# placa_esp_30_pins_V1.net
KiCad netlist of a schematic drawn in EAGLE
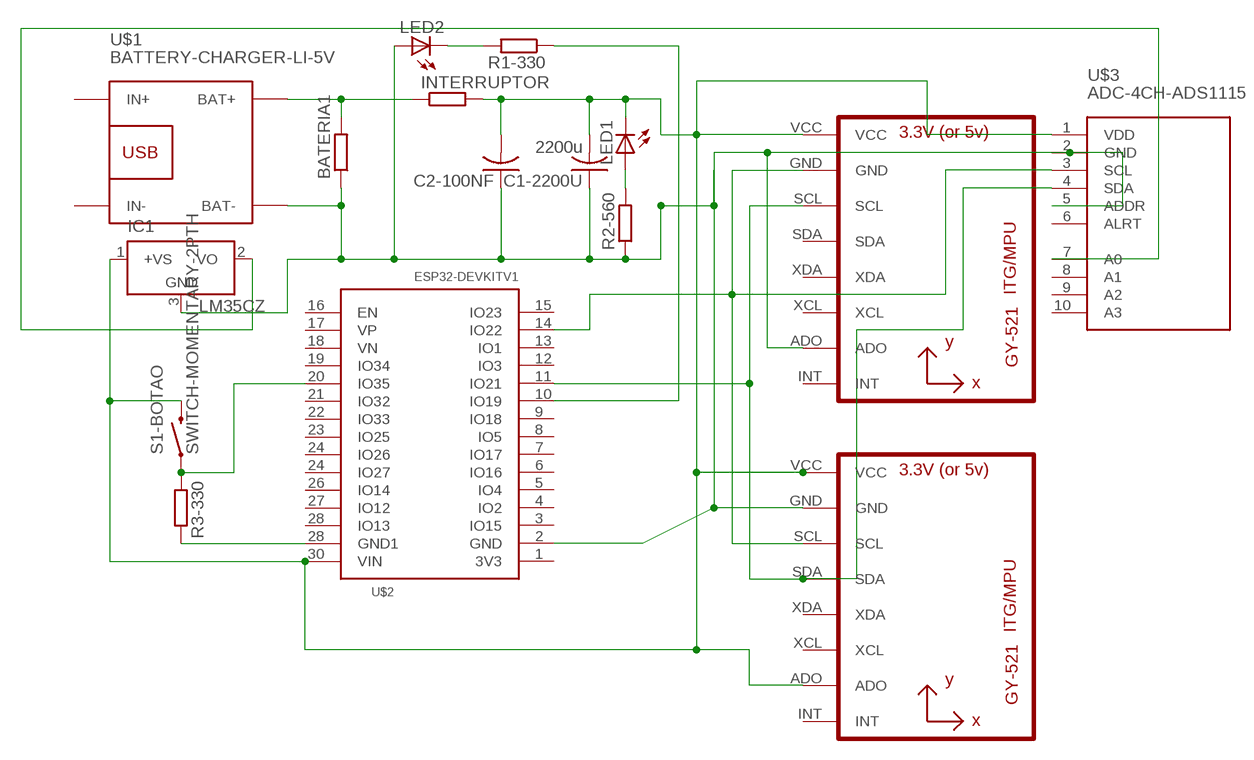
[diagram p0: schematic, sheet 1]

(export (version "E")
  (design (tool "Eeschema 10.0.6"))
  (components
    (comp (ref "BATERIA1")
      (value "R-EU_0207/10")
      (footprint "eagle-import:0207_10")
      (libsource (lib "eagle-import") (part "R-EU_0207/10"))
    )
    (comp (ref "C1-2200U")
      (value "2200u")
      (footprint "eagle-import:C025-060X050")
      (libsource (lib "eagle-import") (part "C-US025-060X050"))
    )
    (comp (ref "C2-100NF")
      (value "C-US025-060X050")
      (footprint "eagle-import:C025-060X050")
      (libsource (lib "eagle-import") (part "C-US025-060X050"))
    )
    (comp (ref "IC1")
      (value "LM35CZ")
      (footprint "eagle-import:TO92")
      (libsource (lib "eagle-import") (part "LM35CZ"))
    )
    (comp (ref "INTERRUPTOR")
      (value "R-EU_0207/7")
      (footprint "eagle-import:0207_7")
      (libsource (lib "eagle-import") (part "R-EU_0207/7"))
    )
    (comp (ref "LED1")
      (value "LEDLD260")
      (footprint "eagle-import:LD260")
      (libsource (lib "eagle-import") (part "LEDLD260"))
    )
    (comp (ref "LED2")
      (value "LEDLD260")
      (footprint "eagle-import:LD260")
      (libsource (lib "eagle-import") (part "LEDLD260"))
    )
    (comp (ref "OXIMETRO")
      (value "GY-521MPU6050")
      (footprint "eagle-import:GY-521")
      (libsource (lib "eagle-import") (part "GY-521MPU6050"))
    )
    (comp (ref "R1-330")
      (value "R-EU_0207/10")
      (footprint "eagle-import:0207_10")
      (libsource (lib "eagle-import") (part "R-EU_0207/10"))
    )
    (comp (ref "R2-560")
      (value "R-EU_0207/10")
      (footprint "eagle-import:0207_10")
      (libsource (lib "eagle-import") (part "R-EU_0207/10"))
    )
    (comp (ref "R3-330")
      (value "R-EU_0207/10")
      (footprint "eagle-import:0207_10")
      (libsource (lib "eagle-import") (part "R-EU_0207/10"))
    )
    (comp (ref "S1-BOTAO")
      (value "SWITCH-MOMENTARY-2PTH")
      (footprint "eagle-import:TACTILE-PTH")
      (libsource (lib "eagle-import") (part "SWITCH-MOMENTARY-2PTH"))
    )
    (comp (ref "U$1")
      (value "BATTERY-CHARGER-LI-5V")
      (footprint "eagle-import:BATTERY-CHARGER-LI-5V")
      (libsource (lib "eagle-import") (part "BATTERY-CHARGER-LI-5V"))
    )
    (comp (ref "U$2")
      (value "ESP32DEVKITV1")
      (footprint "eagle-import:ESP32-DEVKITV1")
      (libsource (lib "eagle-import") (part "ESP32DEVKITV1"))
    )
    (comp (ref "U$3")
      (value "ADC-4CH-ADS1115")
      (footprint "eagle-import:ADC-4CH-ADS1115")
      (libsource (lib "eagle-import") (part "ADC-4CH-ADS1115"))
    )
    (comp (ref "U2")
      (value "GY-521MPU6050")
      (footprint "eagle-import:GY-521")
      (libsource (lib "eagle-import") (part "GY-521MPU6050"))
    )
  )
  (nets
    (net (code "1") (name "Net-(BATERIA1-Pad2)") (class "Default")
      (node (ref "BATERIA1") (pin "2") (pinfunction "2_2") (pintype "passive"))
      (node (ref "INTERRUPTOR") (pin "1") (pinfunction "1_1") (pintype "passive"))
      (node (ref "U$1") (pin "BAT+") (pinfunction "BAT+_BAT+") (pintype "bidirectional"))
    )
    (net (code "2") (name "Net-(IC1-+VS)") (class "Default")
      (node (ref "C1-2200U") (pin "2") (pinfunction "2_2") (pintype "passive"))
      (node (ref "C2-100NF") (pin "2") (pinfunction "2_2") (pintype "passive"))
      (node (ref "IC1") (pin "1") (pinfunction "+VS_1") (pintype "input"))
      (node (ref "INTERRUPTOR") (pin "2") (pinfunction "2_2") (pintype "passive"))
      (node (ref "LED1") (pin "K") (pinfunction "C_K") (pintype "passive"))
      (node (ref "OXIMETRO") (pin "VCC") (pinfunction "VCC_VCC") (pintype "bidirectional"))
      (node (ref "S1-BOTAO") (pin "3") (pinfunction "2_3") (pintype "passive"))
      (node (ref "U$2") (pin "30") (pinfunction "VIN_30") (pintype "bidirectional"))
      (node (ref "U$3") (pin "1") (pinfunction "VDD_1") (pintype "power_in"))
      (node (ref "U2") (pin "ADO") (pinfunction "ADO_ADO") (pintype "bidirectional"))
      (node (ref "U2") (pin "VCC") (pinfunction "VCC_VCC") (pintype "bidirectional"))
    )
    (net (code "3") (name "Net-(IC1-GND)") (class "Default")
      (node (ref "BATERIA1") (pin "1") (pinfunction "1_1") (pintype "passive"))
      (node (ref "C1-2200U") (pin "1") (pinfunction "1_1") (pintype "passive"))
      (node (ref "C2-100NF") (pin "1") (pinfunction "1_1") (pintype "passive"))
      (node (ref "IC1") (pin "3") (pinfunction "GND_3") (pintype "power_in"))
      (node (ref "LED2") (pin "A") (pinfunction "A_A") (pintype "passive"))
      (node (ref "OXIMETRO") (pin "ADO") (pinfunction "ADO_ADO") (pintype "bidirectional"))
      (node (ref "R2-560") (pin "1") (pinfunction "1_1") (pintype "passive"))
      (node (ref "U$1") (pin "BAT-") (pinfunction "BAT-_BAT-") (pintype "bidirectional"))
      (node (ref "U$2") (pin "2") (pinfunction "GND_2") (pintype "bidirectional"))
      (node (ref "U$3") (pin "2") (pinfunction "GND_2") (pintype "power_in"))
      (node (ref "U$3") (pin "5") (pinfunction "ADDR_5") (pintype "bidirectional"))
      (node (ref "U2") (pin "GND") (pinfunction "GND_GND") (pintype "bidirectional"))
    )
    (net (code "4") (name "Net-(IC1-VO)") (class "Default")
      (node (ref "IC1") (pin "2") (pinfunction "VO_2") (pintype "input"))
      (node (ref "U$3") (pin "7") (pinfunction "A0_7") (pintype "input"))
    )
    (net (code "5") (name "Net-(LED1-PadA)") (class "Default")
      (node (ref "LED1") (pin "A") (pinfunction "A_A") (pintype "passive"))
      (node (ref "R2-560") (pin "2") (pinfunction "2_2") (pintype "passive"))
    )
    (net (code "6") (name "Net-(LED2-C)") (class "Default")
      (node (ref "LED2") (pin "K") (pinfunction "C_K") (pintype "passive"))
      (node (ref "R1-330") (pin "2") (pinfunction "2_2") (pintype "passive"))
    )
    (net (code "7") (name "Net-(U$2-GND1)") (class "Default")
      (node (ref "R3-330") (pin "2") (pinfunction "2_2") (pintype "passive"))
      (node (ref "U$2") (pin "28") (pinfunction "GND1_28") (pintype "bidirectional"))
    )
    (net (code "8") (name "Net-(U$2-IO19)") (class "Default")
      (node (ref "R1-330") (pin "1") (pinfunction "1_1") (pintype "passive"))
      (node (ref "U$2") (pin "10") (pinfunction "IO19_10") (pintype "bidirectional"))
    )
    (net (code "9") (name "Net-(U$2-IO21)") (class "Default")
      (node (ref "OXIMETRO") (pin "SCL") (pinfunction "SCL_SCL") (pintype "bidirectional"))
      (node (ref "U$2") (pin "11") (pinfunction "IO21_11") (pintype "bidirectional"))
      (node (ref "U$3") (pin "4") (pinfunction "SDA_4") (pintype "bidirectional"))
      (node (ref "U2") (pin "SDA") (pinfunction "SDA_SDA") (pintype "bidirectional"))
    )
    (net (code "10") (name "Net-(U$2-IO22)") (class "Default")
      (node (ref "OXIMETRO") (pin "GND") (pinfunction "GND_GND") (pintype "bidirectional"))
      (node (ref "U$2") (pin "14") (pinfunction "IO22_14") (pintype "bidirectional"))
      (node (ref "U$3") (pin "3") (pinfunction "SCL_3") (pintype "bidirectional"))
      (node (ref "U2") (pin "SCL") (pinfunction "SCL_SCL") (pintype "bidirectional"))
    )
    (net (code "11") (name "Net-(U$2-IO35)") (class "Default")
      (node (ref "R3-330") (pin "1") (pinfunction "1_1") (pintype "passive"))
      (node (ref "S1-BOTAO") (pin "1") (pinfunction "1_1") (pintype "passive"))
      (node (ref "U$2") (pin "20") (pinfunction "IO35_20") (pintype "bidirectional"))
    )
    (net (code "12") (name "unconnected-(OXIMETRO-PadINT)") (class "Default")
      (node (ref "OXIMETRO") (pin "INT") (pinfunction "INT_INT") (pintype "bidirectional"))
    )
    (net (code "13") (name "unconnected-(OXIMETRO-PadSDA)") (class "Default")
      (node (ref "OXIMETRO") (pin "SDA") (pinfunction "SDA_SDA") (pintype "bidirectional"))
    )
    (net (code "14") (name "unconnected-(OXIMETRO-PadXCL)") (class "Default")
      (node (ref "OXIMETRO") (pin "XCL") (pinfunction "XCL_XCL") (pintype "bidirectional"))
    )
    (net (code "15") (name "unconnected-(OXIMETRO-PadXDA)") (class "Default")
      (node (ref "OXIMETRO") (pin "XDA") (pinfunction "XDA_XDA") (pintype "bidirectional"))
    )
    (net (code "16") (name "unconnected-(U$1-PadIN+)") (class "Default")
      (node (ref "U$1") (pin "IN+") (pinfunction "IN+_IN+") (pintype "bidirectional"))
    )
    (net (code "17") (name "unconnected-(U$1-PadIN-)") (class "Default")
      (node (ref "U$1") (pin "IN-") (pinfunction "IN-_IN-") (pintype "bidirectional"))
    )
    (net (code "18") (name "unconnected-(U$2-3V3-Pad1)") (class "Default")
      (node (ref "U$2") (pin "1") (pinfunction "3V3_1") (pintype "bidirectional"))
    )
    (net (code "19") (name "unconnected-(U$2-EN-Pad16)") (class "Default")
      (node (ref "U$2") (pin "16") (pinfunction "EN_16") (pintype "bidirectional"))
    )
    (net (code "20") (name "unconnected-(U$2-IO1-Pad13)") (class "Default")
      (node (ref "U$2") (pin "13") (pinfunction "IO1_13") (pintype "bidirectional"))
    )
    (net (code "21") (name "unconnected-(U$2-IO2-Pad4)") (class "Default")
      (node (ref "U$2") (pin "4") (pinfunction "IO2_4") (pintype "bidirectional"))
    )
    (net (code "22") (name "unconnected-(U$2-IO3-Pad12)") (class "Default")
      (node (ref "U$2") (pin "12") (pinfunction "IO3_12") (pintype "bidirectional"))
    )
    (net (code "23") (name "unconnected-(U$2-IO4-Pad5)") (class "Default")
      (node (ref "U$2") (pin "5") (pinfunction "IO4_5") (pintype "bidirectional"))
    )
    (net (code "24") (name "unconnected-(U$2-IO5-Pad8)") (class "Default")
      (node (ref "U$2") (pin "8") (pinfunction "IO5_8") (pintype "bidirectional"))
    )
    (net (code "25") (name "unconnected-(U$2-IO12-Pad27)") (class "Default")
      (node (ref "U$2") (pin "27") (pinfunction "IO12_27") (pintype "bidirectional"))
    )
    (net (code "26") (name "unconnected-(U$2-IO13-Pad28)") (class "Default")
      (node (ref "U$2") (pin "28") (pinfunction "IO13_28") (pintype "bidirectional"))
    )
    (net (code "27") (name "unconnected-(U$2-IO14-Pad26)") (class "Default")
      (node (ref "U$2") (pin "26") (pinfunction "IO14_26") (pintype "bidirectional"))
    )
    (net (code "28") (name "unconnected-(U$2-IO15-Pad3)") (class "Default")
      (node (ref "U$2") (pin "3") (pinfunction "IO15_3") (pintype "bidirectional"))
    )
    (net (code "29") (name "unconnected-(U$2-IO16-Pad6)") (class "Default")
      (node (ref "U$2") (pin "6") (pinfunction "IO16_6") (pintype "bidirectional"))
    )
    (net (code "30") (name "unconnected-(U$2-IO17-Pad7)") (class "Default")
      (node (ref "U$2") (pin "7") (pinfunction "IO17_7") (pintype "bidirectional"))
    )
    (net (code "31") (name "unconnected-(U$2-IO18-Pad9)") (class "Default")
      (node (ref "U$2") (pin "9") (pinfunction "IO18_9") (pintype "bidirectional"))
    )
    (net (code "32") (name "unconnected-(U$2-IO23-Pad15)") (class "Default")
      (node (ref "U$2") (pin "15") (pinfunction "IO23_15") (pintype "bidirectional"))
    )
    (net (code "33") (name "unconnected-(U$2-IO25-Pad23)") (class "Default")
      (node (ref "U$2") (pin "23") (pinfunction "IO25_23") (pintype "bidirectional"))
    )
    (net (code "34") (name "unconnected-(U$2-IO26-Pad24)") (class "Default")
      (node (ref "U$2") (pin "24") (pinfunction "IO26_24") (pintype "bidirectional"))
    )
    (net (code "35") (name "unconnected-(U$2-IO27-Pad24)") (class "Default")
      (node (ref "U$2") (pin "24") (pinfunction "IO27_24") (pintype "bidirectional"))
    )
    (net (code "36") (name "unconnected-(U$2-IO32-Pad21)") (class "Default")
      (node (ref "U$2") (pin "21") (pinfunction "IO32_21") (pintype "bidirectional"))
    )
    (net (code "37") (name "unconnected-(U$2-IO33-Pad22)") (class "Default")
      (node (ref "U$2") (pin "22") (pinfunction "IO33_22") (pintype "bidirectional"))
    )
    (net (code "38") (name "unconnected-(U$2-IO34-Pad19)") (class "Default")
      (node (ref "U$2") (pin "19") (pinfunction "IO34_19") (pintype "bidirectional"))
    )
    (net (code "39") (name "unconnected-(U$2-VN-Pad18)") (class "Default")
      (node (ref "U$2") (pin "18") (pinfunction "VN_18") (pintype "bidirectional"))
    )
    (net (code "40") (name "unconnected-(U$2-VP-Pad17)") (class "Default")
      (node (ref "U$2") (pin "17") (pinfunction "VP_17") (pintype "bidirectional"))
    )
    (net (code "41") (name "unconnected-(U$3-A1-Pad8)") (class "Default")
      (node (ref "U$3") (pin "8") (pinfunction "A1_8") (pintype "input"))
    )
    (net (code "42") (name "unconnected-(U$3-A2-Pad9)") (class "Default")
      (node (ref "U$3") (pin "9") (pinfunction "A2_9") (pintype "input"))
    )
    (net (code "43") (name "unconnected-(U$3-A3-Pad10)") (class "Default")
      (node (ref "U$3") (pin "10") (pinfunction "A3_10") (pintype "input"))
    )
    (net (code "44") (name "unconnected-(U$3-ALRT-Pad6)") (class "Default")
      (node (ref "U$3") (pin "6") (pinfunction "ALRT_6") (pintype "bidirectional"))
    )
    (net (code "45") (name "unconnected-(U2-PadINT)") (class "Default")
      (node (ref "U2") (pin "INT") (pinfunction "INT_INT") (pintype "bidirectional"))
    )
    (net (code "46") (name "unconnected-(U2-PadXCL)") (class "Default")
      (node (ref "U2") (pin "XCL") (pinfunction "XCL_XCL") (pintype "bidirectional"))
    )
    (net (code "47") (name "unconnected-(U2-PadXDA)") (class "Default")
      (node (ref "U2") (pin "XDA") (pinfunction "XDA_XDA") (pintype "bidirectional"))
    )
  )
)
